# SCH_TestCharlieplex1_2025-11-02.net
KiCad netlist of a schematic drawn in EasyEDA
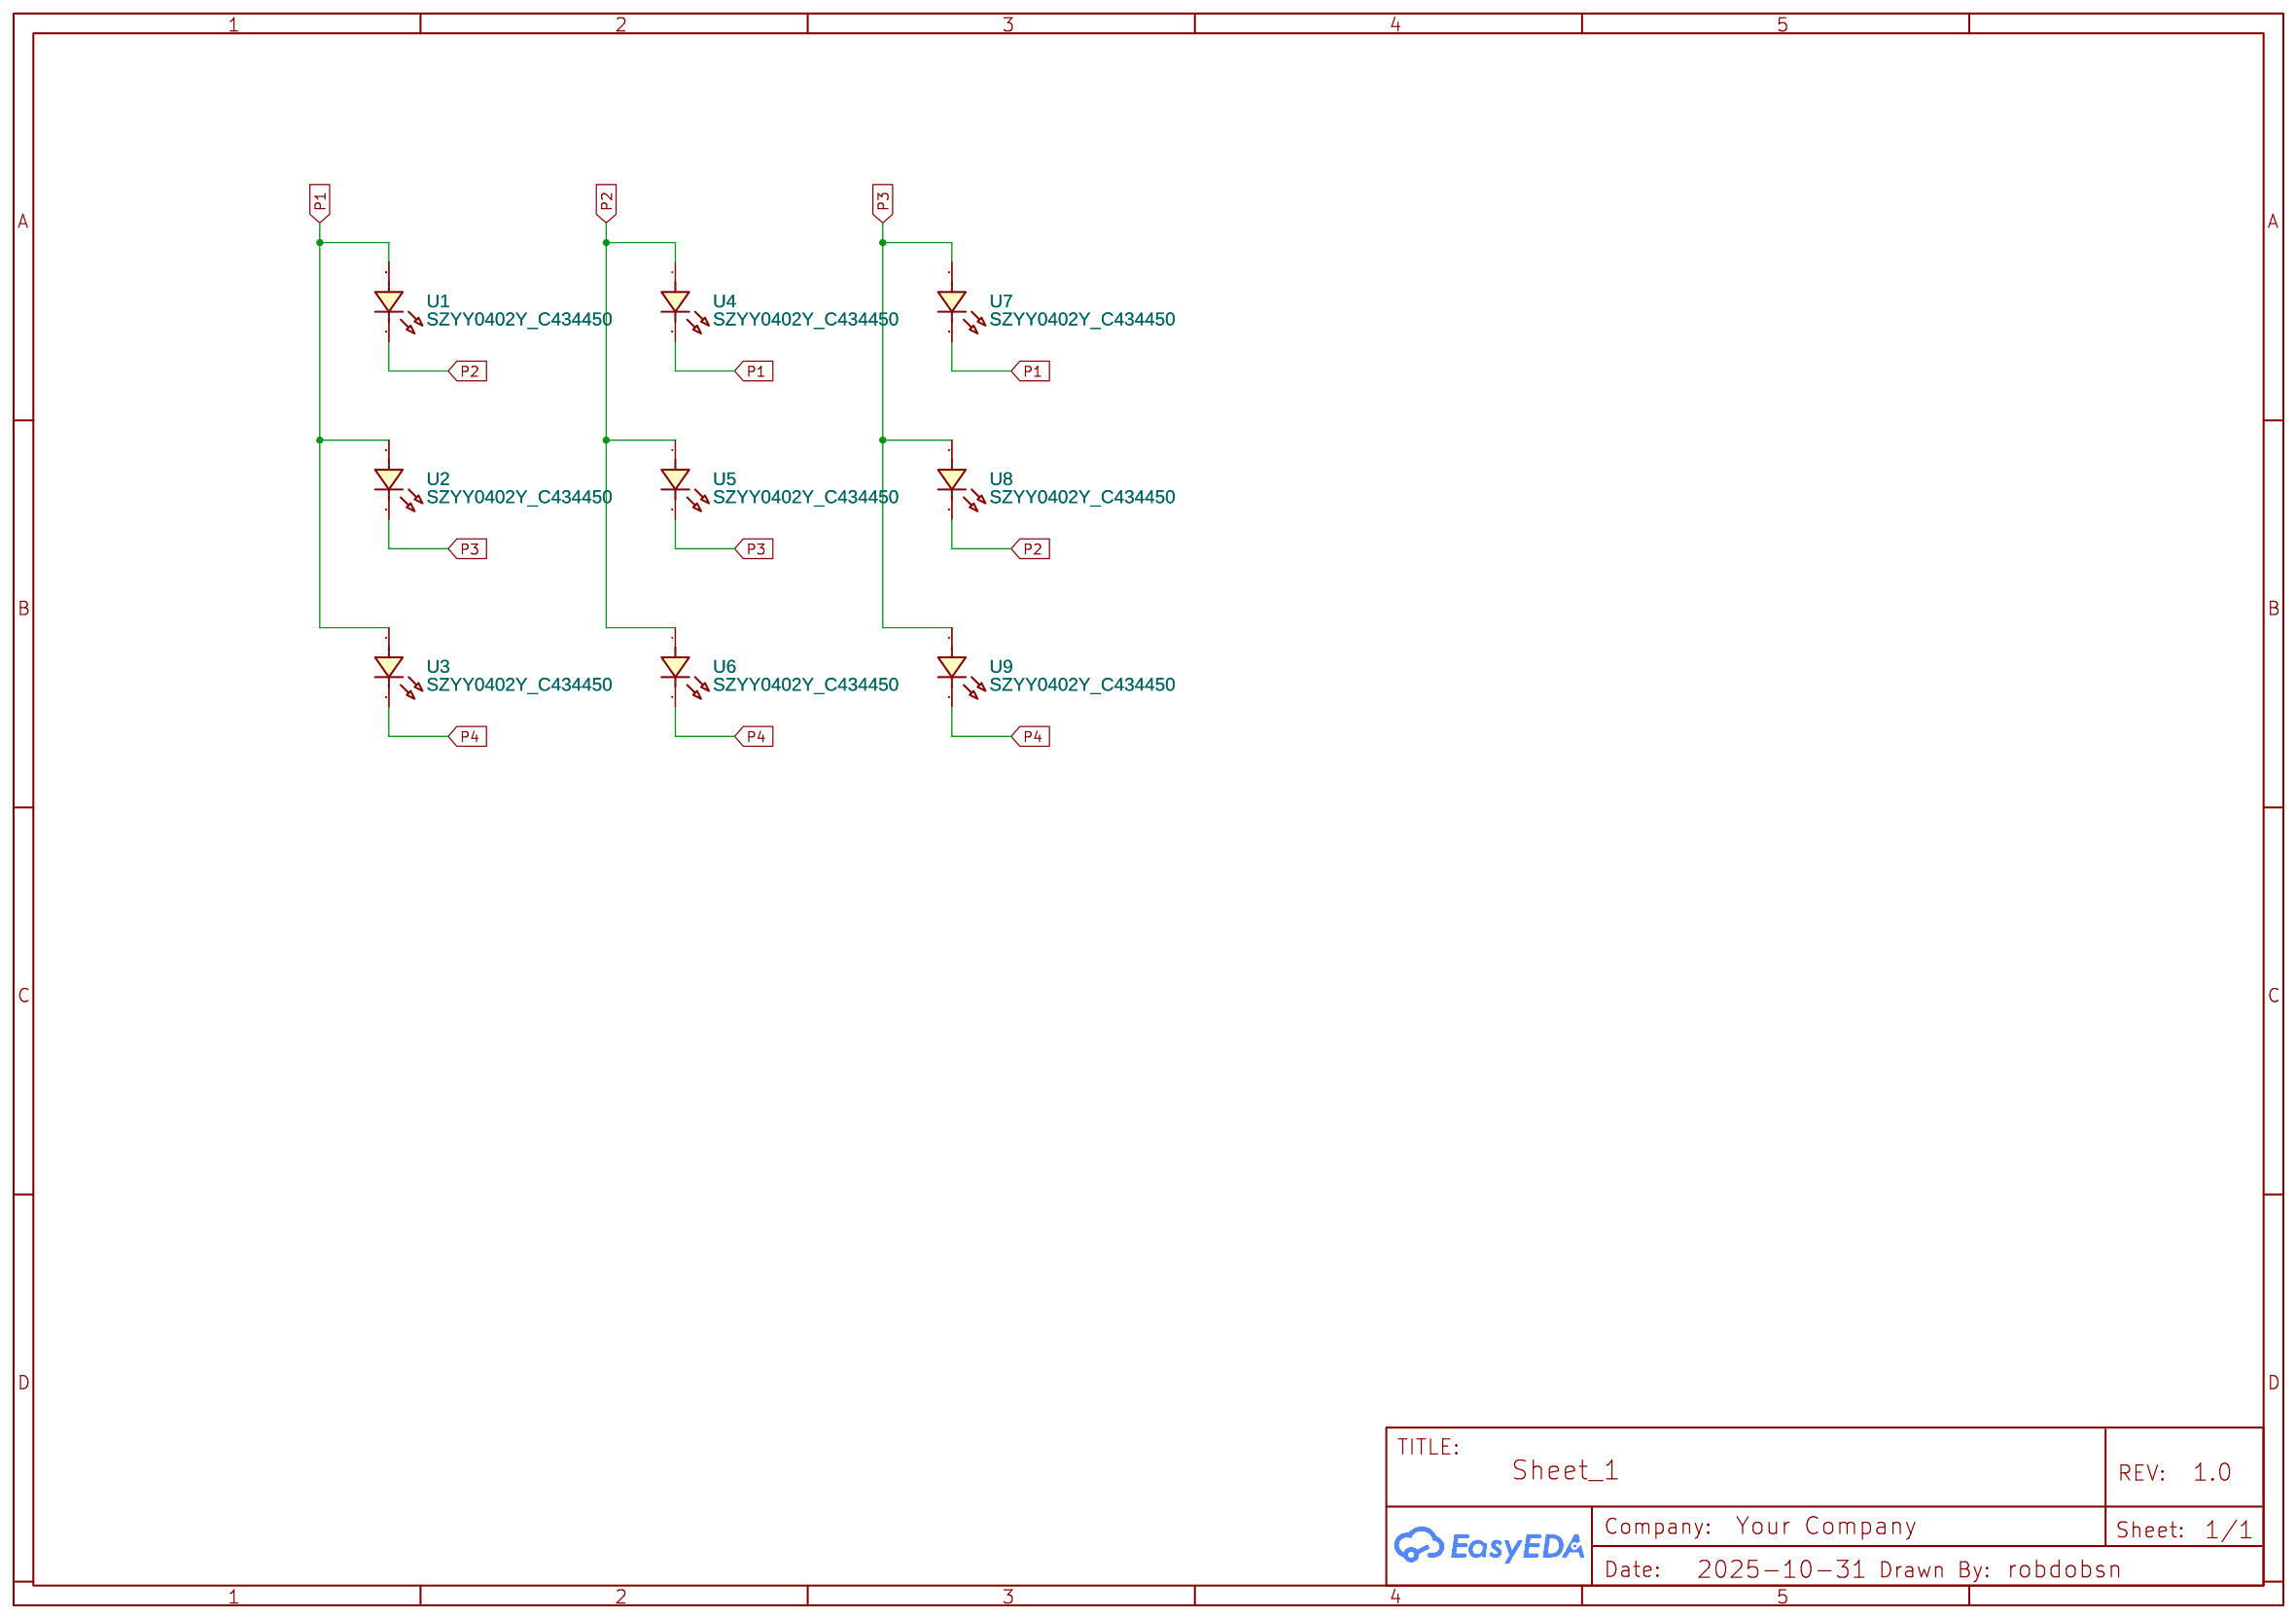
[diagram p0: schematic sheet]

(export (version "E")
  (design (tool "Eeschema 10.0.6"))
  (components
    (comp (ref "U1")
      (value "SZYY0402Y_C434450")
      (fields (field (name "Manufacturer Part") "SZYY0402Y") (field (name "Manufacturer") "yongyu(永裕光电)"))
      (libsource (lib "") (part "SZYY0402Y_C434450"))
    )
    (comp (ref "U2")
      (value "SZYY0402Y_C434450")
      (fields (field (name "Manufacturer Part") "SZYY0402Y") (field (name "Manufacturer") "yongyu(永裕光电)"))
      (libsource (lib "") (part "SZYY0402Y_C434450"))
    )
    (comp (ref "U3")
      (value "SZYY0402Y_C434450")
      (fields (field (name "Manufacturer Part") "SZYY0402Y") (field (name "Manufacturer") "yongyu(永裕光电)"))
      (libsource (lib "") (part "SZYY0402Y_C434450"))
    )
    (comp (ref "U4")
      (value "SZYY0402Y_C434450")
      (fields (field (name "Manufacturer Part") "SZYY0402Y") (field (name "Manufacturer") "yongyu(永裕光电)"))
      (libsource (lib "") (part "SZYY0402Y_C434450"))
    )
    (comp (ref "U5")
      (value "SZYY0402Y_C434450")
      (fields (field (name "Manufacturer Part") "SZYY0402Y") (field (name "Manufacturer") "yongyu(永裕光电)"))
      (libsource (lib "") (part "SZYY0402Y_C434450"))
    )
    (comp (ref "U6")
      (value "SZYY0402Y_C434450")
      (fields (field (name "Manufacturer Part") "SZYY0402Y") (field (name "Manufacturer") "yongyu(永裕光电)"))
      (libsource (lib "") (part "SZYY0402Y_C434450"))
    )
    (comp (ref "U7")
      (value "SZYY0402Y_C434450")
      (fields (field (name "Manufacturer Part") "SZYY0402Y") (field (name "Manufacturer") "yongyu(永裕光电)"))
      (libsource (lib "") (part "SZYY0402Y_C434450"))
    )
    (comp (ref "U8")
      (value "SZYY0402Y_C434450")
      (fields (field (name "Manufacturer Part") "SZYY0402Y") (field (name "Manufacturer") "yongyu(永裕光电)"))
      (libsource (lib "") (part "SZYY0402Y_C434450"))
    )
    (comp (ref "U9")
      (value "SZYY0402Y_C434450")
      (fields (field (name "Manufacturer Part") "SZYY0402Y") (field (name "Manufacturer") "yongyu(永裕光电)"))
      (libsource (lib "") (part "SZYY0402Y_C434450"))
    )
  )
  (nets
    (net (code "1") (name "P1") (class "Default")
      (node (ref "U1") (pin "1") (pinfunction "A_1") (pintype "unspecified"))
      (node (ref "U2") (pin "1") (pinfunction "A_1") (pintype "unspecified"))
      (node (ref "U3") (pin "1") (pinfunction "A_1") (pintype "unspecified"))
      (node (ref "U4") (pin "2") (pinfunction "K_2") (pintype "unspecified"))
      (node (ref "U7") (pin "2") (pinfunction "K_2") (pintype "unspecified"))
    )
    (net (code "2") (name "P2") (class "Default")
      (node (ref "U1") (pin "2") (pinfunction "K_2") (pintype "unspecified"))
      (node (ref "U4") (pin "1") (pinfunction "A_1") (pintype "unspecified"))
      (node (ref "U5") (pin "1") (pinfunction "A_1") (pintype "unspecified"))
      (node (ref "U6") (pin "1") (pinfunction "A_1") (pintype "unspecified"))
      (node (ref "U8") (pin "2") (pinfunction "K_2") (pintype "unspecified"))
    )
    (net (code "3") (name "P3") (class "Default")
      (node (ref "U2") (pin "2") (pinfunction "K_2") (pintype "unspecified"))
      (node (ref "U5") (pin "2") (pinfunction "K_2") (pintype "unspecified"))
      (node (ref "U7") (pin "1") (pinfunction "A_1") (pintype "unspecified"))
      (node (ref "U8") (pin "1") (pinfunction "A_1") (pintype "unspecified"))
      (node (ref "U9") (pin "1") (pinfunction "A_1") (pintype "unspecified"))
    )
    (net (code "4") (name "P4") (class "Default")
      (node (ref "U3") (pin "2") (pinfunction "K_2") (pintype "unspecified"))
      (node (ref "U6") (pin "2") (pinfunction "K_2") (pintype "unspecified"))
      (node (ref "U9") (pin "2") (pinfunction "K_2") (pintype "unspecified"))
    )
  )
)
